# DC_DC_V1_4_2-1_top.net
KiCad netlist of a schematic drawn in EAGLE
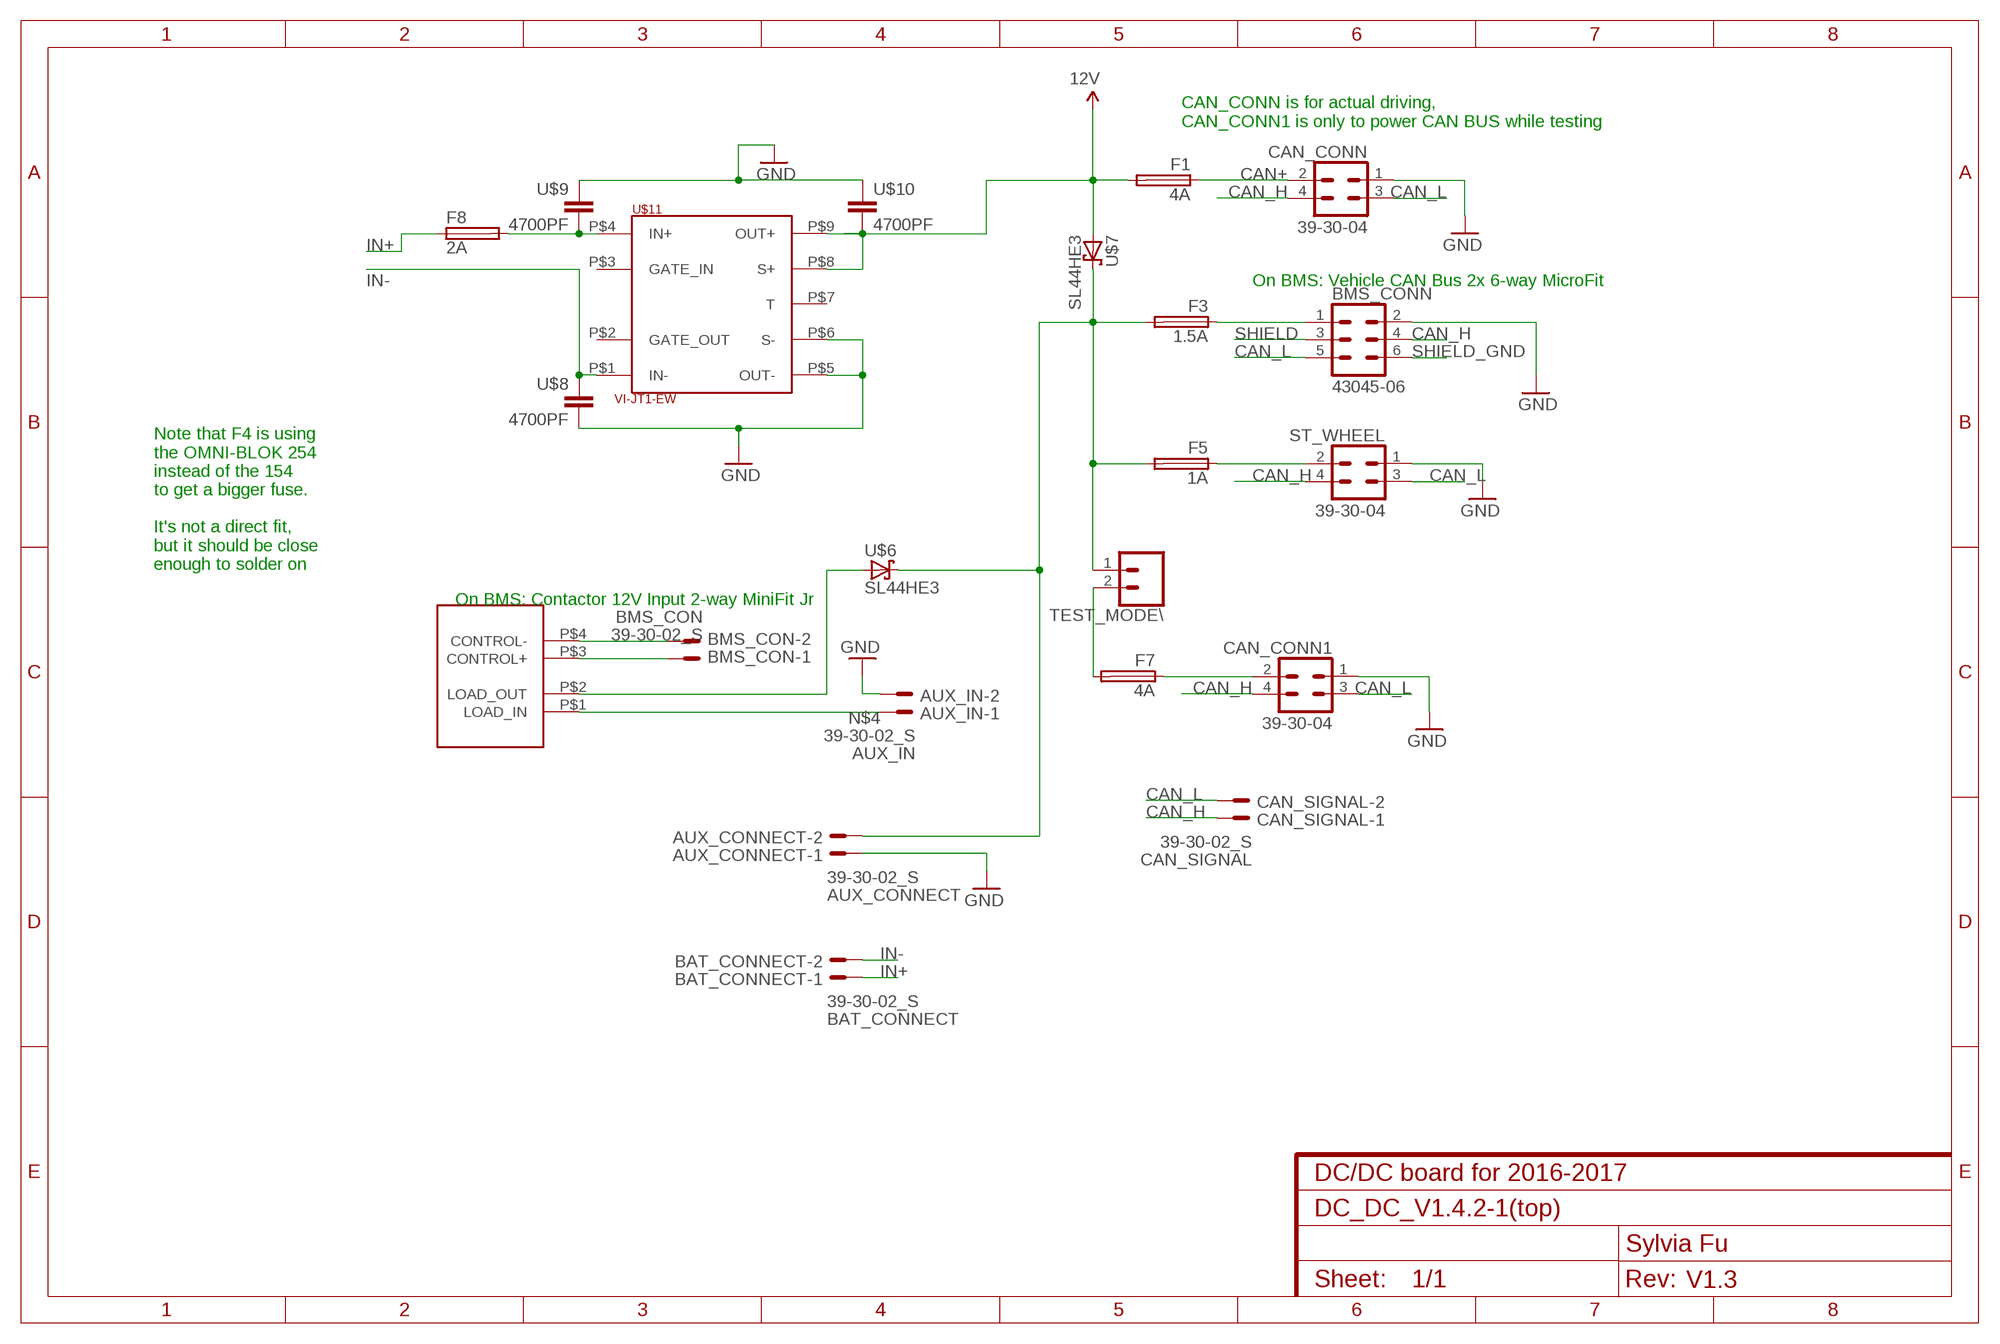
[diagram p0: schematic, sheet 1]

(export (version "E")
  (design (tool "Eeschema 10.0.6"))
  (components
    (comp (ref "AUX_CONNECT")
      (value "39-30-02_S")
      (footprint "eagle-import:39-30-_02_")
      (libsource (lib "eagle-import") (part "39-30-?02?_S"))
    )
    (comp (ref "AUX_IN")
      (value "39-30-02_S")
      (footprint "eagle-import:39-30-_02_")
      (libsource (lib "eagle-import") (part "39-30-?02?_S"))
    )
    (comp (ref "BAT_CONNECT")
      (value "39-30-02_S")
      (footprint "eagle-import:39-30-_02_")
      (libsource (lib "eagle-import") (part "39-30-?02?_S"))
    )
    (comp (ref "BMS_CON")
      (value "39-30-02_S")
      (footprint "eagle-import:39-30-_02_")
      (libsource (lib "eagle-import") (part "39-30-?02?_S"))
    )
    (comp (ref "BMS_CONN")
      (value "43045-06")
      (footprint "eagle-import:43045-06")
      (libsource (lib "eagle-import") (part "43045-06"))
    )
    (comp (ref "CAN_CONN")
      (value "39-30-04")
      (footprint "eagle-import:39-30-_04_")
      (libsource (lib "eagle-import") (part "39-30-?04?"))
    )
    (comp (ref "CAN_CONN1")
      (value "39-30-04")
      (footprint "eagle-import:39-30-_04_")
      (libsource (lib "eagle-import") (part "39-30-?04?"))
    )
    (comp (ref "CAN_SIGNAL")
      (value "39-30-02_S")
      (footprint "eagle-import:39-30-_02_")
      (libsource (lib "eagle-import") (part "39-30-?02?_S"))
    )
    (comp (ref "F1")
      (value "4A")
      (footprint "eagle-import:OMNIBLOK")
      (libsource (lib "eagle-import") (part "SMD-MICRO-FUSE-BLOCK"))
    )
    (comp (ref "F3")
      (value "1.5A")
      (footprint "eagle-import:OMNIBLOK")
      (libsource (lib "eagle-import") (part "SMD-MICRO-FUSE-BLOCK"))
    )
    (comp (ref "F5")
      (value "1A")
      (footprint "eagle-import:OMNIBLOK")
      (libsource (lib "eagle-import") (part "SMD-MICRO-FUSE-BLOCK"))
    )
    (comp (ref "F7")
      (value "4A")
      (footprint "eagle-import:OMNIBLOK")
      (libsource (lib "eagle-import") (part "SMD-MICRO-FUSE-BLOCK"))
    )
    (comp (ref "F8")
      (value "2A")
      (footprint "eagle-import:OMNIBLOK")
      (libsource (lib "eagle-import") (part "SMD-MICRO-FUSE-BLOCK"))
    )
    (comp (ref "ST_WHEEL")
      (value "39-30-04")
      (footprint "eagle-import:39-30-_04_")
      (libsource (lib "eagle-import") (part "39-30-?04?"))
    )
    (comp (ref "TEST_MODE\\")
      (value "CONN_02")
      (footprint "eagle-import:1X02")
      (libsource (lib "eagle-import") (part "CONN_02"))
    )
    (comp (ref "U$2")
      (value "MPDCD3B")
      (footprint "eagle-import:MPDCD3B")
      (libsource (lib "eagle-import") (part "MPDCD3B"))
    )
    (comp (ref "U$6")
      (value "SL44HE3")
      (footprint "eagle-import:SMC")
      (libsource (lib "eagle-import") (part "SL44HE3"))
    )
    (comp (ref "U$7")
      (value "SL44HE3")
      (footprint "eagle-import:SMC")
      (libsource (lib "eagle-import") (part "SL44HE3"))
    )
    (comp (ref "U$8")
      (value "4700PF")
      (footprint "eagle-import:Y2_CAP")
      (libsource (lib "eagle-import") (part "4700PF"))
    )
    (comp (ref "U$9")
      (value "4700PF")
      (footprint "eagle-import:Y2_CAP")
      (libsource (lib "eagle-import") (part "4700PF"))
    )
    (comp (ref "U$10")
      (value "4700PF")
      (footprint "eagle-import:Y2_CAP")
      (libsource (lib "eagle-import") (part "4700PF"))
    )
    (comp (ref "U$11")
      (value "VI-JT1-EW")
      (footprint "eagle-import:VI-J00")
      (libsource (lib "eagle-import") (part "VI-JT1-EW"))
    )
  )
  (nets
    (net (code "1") (name "/CAN+") (class "Default")
      (node (ref "CAN_CONN") (pin "2") (pinfunction "2_2") (pintype "passive"))
      (node (ref "F1") (pin "P$1") (pinfunction "1_P$1") (pintype "passive"))
    )
    (net (code "2") (name "/CAN_H") (class "Default")
      (node (ref "BMS_CONN") (pin "4") (pinfunction "4_4") (pintype "passive"))
      (node (ref "CAN_CONN") (pin "4") (pinfunction "4_4") (pintype "passive"))
      (node (ref "CAN_CONN1") (pin "4") (pinfunction "4_4") (pintype "passive"))
      (node (ref "CAN_SIGNAL") (pin "1") (pinfunction "P_1") (pintype "passive"))
      (node (ref "ST_WHEEL") (pin "4") (pinfunction "4_4") (pintype "passive"))
    )
    (net (code "3") (name "/CAN_L") (class "Default")
      (node (ref "BMS_CONN") (pin "5") (pinfunction "5_5") (pintype "passive"))
      (node (ref "CAN_CONN") (pin "3") (pinfunction "3_3") (pintype "passive"))
      (node (ref "CAN_CONN1") (pin "3") (pinfunction "3_3") (pintype "passive"))
      (node (ref "CAN_SIGNAL") (pin "2") (pinfunction "P_2") (pintype "passive"))
      (node (ref "ST_WHEEL") (pin "3") (pinfunction "3_3") (pintype "passive"))
    )
    (net (code "4") (name "/IN+") (class "Default")
      (node (ref "BAT_CONNECT") (pin "1") (pinfunction "P_1") (pintype "passive"))
      (node (ref "F8") (pin "P$1") (pinfunction "1_P$1") (pintype "passive"))
    )
    (net (code "5") (name "/IN-") (class "Default")
      (node (ref "BAT_CONNECT") (pin "2") (pinfunction "P_2") (pintype "passive"))
      (node (ref "U$11") (pin "P$1") (pinfunction "IN-_P$1") (pintype "bidirectional"))
      (node (ref "U$8") (pin "P$1") (pinfunction "1_P$1") (pintype "passive"))
    )
    (net (code "6") (name "/N$4") (class "Default")
      (node (ref "U$2") (pin "P$2") (pinfunction "LOAD_OUT_P$2") (pintype "bidirectional"))
      (node (ref "U$6") (pin "A") (pinfunction "A_A") (pintype "passive"))
    )
    (net (code "7") (name "/SHIELD") (class "Default")
      (node (ref "BMS_CONN") (pin "3") (pinfunction "3_3") (pintype "passive"))
    )
    (net (code "8") (name "/SHIELD_GND") (class "Default")
      (node (ref "BMS_CONN") (pin "6") (pinfunction "6_6") (pintype "passive"))
    )
    (net (code "9") (name "12V") (class "Default")
      (node (ref "F1") (pin "P$2") (pinfunction "2_P$2") (pintype "passive"))
      (node (ref "U$10") (pin "P$2") (pinfunction "2_P$2") (pintype "passive"))
      (node (ref "U$11") (pin "P$8") (pinfunction "S+_P$8") (pintype "bidirectional"))
      (node (ref "U$11") (pin "P$9") (pinfunction "OUT+_P$9") (pintype "bidirectional"))
      (node (ref "U$7") (pin "A") (pinfunction "A_A") (pintype "passive"))
    )
    (net (code "10") (name "GND") (class "Default")
      (node (ref "AUX_CONNECT") (pin "1") (pinfunction "P_1") (pintype "passive"))
      (node (ref "AUX_IN") (pin "2") (pinfunction "P_2") (pintype "passive"))
      (node (ref "BMS_CONN") (pin "2") (pinfunction "2_2") (pintype "passive"))
      (node (ref "CAN_CONN") (pin "1") (pinfunction "1_1") (pintype "passive"))
      (node (ref "CAN_CONN1") (pin "1") (pinfunction "1_1") (pintype "passive"))
      (node (ref "ST_WHEEL") (pin "1") (pinfunction "1_1") (pintype "passive"))
      (node (ref "U$10") (pin "P$1") (pinfunction "1_P$1") (pintype "passive"))
      (node (ref "U$11") (pin "P$5") (pinfunction "OUT-_P$5") (pintype "bidirectional"))
      (node (ref "U$11") (pin "P$6") (pinfunction "S-_P$6") (pintype "bidirectional"))
      (node (ref "U$8") (pin "P$2") (pinfunction "2_P$2") (pintype "passive"))
      (node (ref "U$9") (pin "P$1") (pinfunction "1_P$1") (pintype "passive"))
    )
    (net (code "11") (name "Net-(AUX_CONNECTB-P)") (class "Default")
      (node (ref "AUX_CONNECT") (pin "2") (pinfunction "P_2") (pintype "passive"))
      (node (ref "F3") (pin "P$2") (pinfunction "2_P$2") (pintype "passive"))
      (node (ref "F5") (pin "P$2") (pinfunction "2_P$2") (pintype "passive"))
      (node (ref "TEST_MODE\\") (pin "1") (pinfunction "1_1") (pintype "passive"))
      (node (ref "U$6") (pin "C") (pinfunction "C_C") (pintype "passive"))
      (node (ref "U$7") (pin "C") (pinfunction "C_C") (pintype "passive"))
    )
    (net (code "12") (name "Net-(AUX_INA-P)") (class "Default")
      (node (ref "AUX_IN") (pin "1") (pinfunction "P_1") (pintype "passive"))
      (node (ref "U$2") (pin "P$1") (pinfunction "LOAD_IN_P$1") (pintype "bidirectional"))
    )
    (net (code "13") (name "Net-(BMS_CONA-P)") (class "Default")
      (node (ref "BMS_CON") (pin "1") (pinfunction "P_1") (pintype "passive"))
      (node (ref "U$2") (pin "P$3") (pinfunction "CONTROL+_P$3") (pintype "bidirectional"))
    )
    (net (code "14") (name "Net-(BMS_CONB-P)") (class "Default")
      (node (ref "BMS_CON") (pin "2") (pinfunction "P_2") (pintype "passive"))
      (node (ref "U$2") (pin "P$4") (pinfunction "CONTROL-_P$4") (pintype "bidirectional"))
    )
    (net (code "15") (name "Net-(F3-1)") (class "Default")
      (node (ref "BMS_CONN") (pin "1") (pinfunction "1_1") (pintype "passive"))
      (node (ref "F3") (pin "P$1") (pinfunction "1_P$1") (pintype "passive"))
    )
    (net (code "16") (name "Net-(F5-1)") (class "Default")
      (node (ref "F5") (pin "P$1") (pinfunction "1_P$1") (pintype "passive"))
      (node (ref "ST_WHEEL") (pin "2") (pinfunction "2_2") (pintype "passive"))
    )
    (net (code "17") (name "Net-(F7-1)") (class "Default")
      (node (ref "CAN_CONN1") (pin "2") (pinfunction "2_2") (pintype "passive"))
      (node (ref "F7") (pin "P$1") (pinfunction "1_P$1") (pintype "passive"))
    )
    (net (code "18") (name "Net-(F7-2)") (class "Default")
      (node (ref "F7") (pin "P$2") (pinfunction "2_P$2") (pintype "passive"))
      (node (ref "TEST_MODE\\") (pin "2") (pinfunction "2_2") (pintype "passive"))
    )
    (net (code "19") (name "Net-(F8-2)") (class "Default")
      (node (ref "F8") (pin "P$2") (pinfunction "2_P$2") (pintype "passive"))
      (node (ref "U$11") (pin "P$4") (pinfunction "IN+_P$4") (pintype "bidirectional"))
      (node (ref "U$9") (pin "P$2") (pinfunction "2_P$2") (pintype "passive"))
    )
    (net (code "20") (name "unconnected-(U$11-GATE_IN-PadP$3)") (class "Default")
      (node (ref "U$11") (pin "P$3") (pinfunction "GATE_IN_P$3") (pintype "bidirectional"))
    )
    (net (code "21") (name "unconnected-(U$11-GATE_OUT-PadP$2)") (class "Default")
      (node (ref "U$11") (pin "P$2") (pinfunction "GATE_OUT_P$2") (pintype "bidirectional"))
    )
    (net (code "22") (name "unconnected-(U$11-T-PadP$7)") (class "Default")
      (node (ref "U$11") (pin "P$7") (pinfunction "T_P$7") (pintype "bidirectional"))
    )
  )
)
